# Connector-side-2.net
KiCad netlist of a schematic drawn in Altium Designer
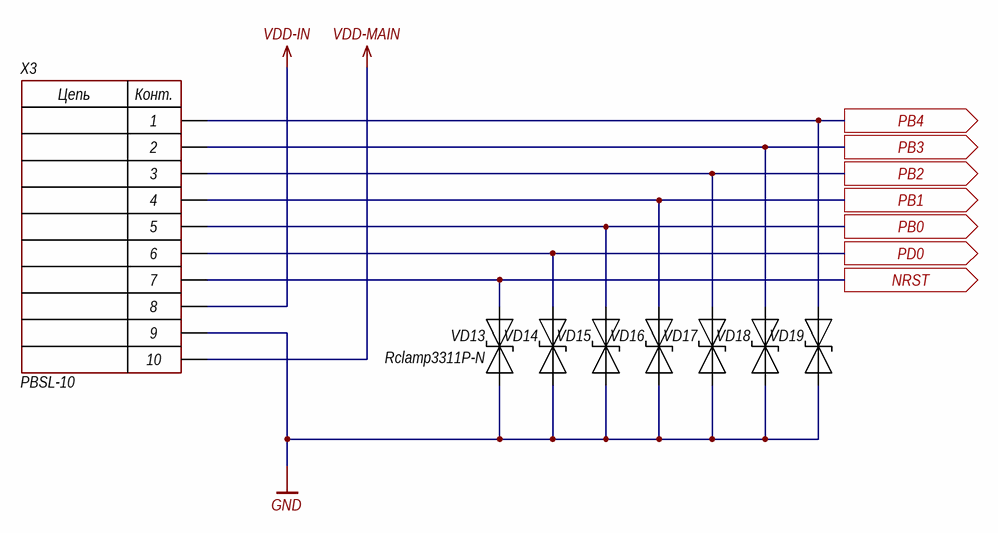
[diagram p0: Connector-side-2.SchDoc]

(export (version "E")
  (design (tool "Eeschema 10.0.6"))
  (components
    (comp (ref "VD13")
      (value "Rclamp3311P-N")
      (footprint "DFN1006-2")
      (fields (field (name "MANUFACTURER") "BORN"))
      (libsource (lib "Diods") (part "TVS-diod"))
    )
    (comp (ref "VD14")
      (value "Rclamp3311P-N")
      (footprint "DFN1006-2")
      (fields (field (name "MANUFACTURER") "BORN"))
      (libsource (lib "Diods") (part "TVS-diod"))
    )
    (comp (ref "VD15")
      (value "Rclamp3311P-N")
      (footprint "DFN1006-2")
      (fields (field (name "MANUFACTURER") "BORN"))
      (libsource (lib "Diods") (part "TVS-diod"))
    )
    (comp (ref "VD16")
      (value "Rclamp3311P-N")
      (footprint "DFN1006-2")
      (fields (field (name "MANUFACTURER") "BORN"))
      (libsource (lib "Diods") (part "TVS-diod"))
    )
    (comp (ref "VD17")
      (value "Rclamp3311P-N")
      (footprint "DFN1006-2")
      (fields (field (name "MANUFACTURER") "BORN"))
      (libsource (lib "Diods") (part "TVS-diod"))
    )
    (comp (ref "VD18")
      (value "Rclamp3311P-N")
      (footprint "DFN1006-2")
      (fields (field (name "MANUFACTURER") "BORN"))
      (libsource (lib "Diods") (part "TVS-diod"))
    )
    (comp (ref "VD19")
      (value "Rclamp3311P-N")
      (footprint "DFN1006-2")
      (fields (field (name "MANUFACTURER") "BORN"))
      (libsource (lib "Diods") (part "TVS-diod"))
    )
    (comp (ref "X3")
      (value "PBSL-10")
      (footprint "CON: PBSL-10")
      (libsource (lib "Connectors") (part "10-Connector"))
    )
  )
  (nets
    (net (code "1") (name "/NRST") (class "Default")
      (node (ref "VD13") (pin "2") (pinfunction "C_2") (pintype "passive"))
      (node (ref "X3") (pin "7") (pinfunction "7_7") (pintype "passive"))
    )
    (net (code "2") (name "/PB0") (class "Default")
      (node (ref "VD15") (pin "2") (pinfunction "C_2") (pintype "passive"))
      (node (ref "X3") (pin "5") (pinfunction "5_5") (pintype "passive"))
    )
    (net (code "3") (name "/PB1") (class "Default")
      (node (ref "VD16") (pin "2") (pinfunction "C_2") (pintype "passive"))
      (node (ref "X3") (pin "4") (pinfunction "4_4") (pintype "passive"))
    )
    (net (code "4") (name "/PB2") (class "Default")
      (node (ref "VD17") (pin "2") (pinfunction "C_2") (pintype "passive"))
      (node (ref "X3") (pin "3") (pinfunction "3_3") (pintype "passive"))
    )
    (net (code "5") (name "/PB3") (class "Default")
      (node (ref "VD18") (pin "2") (pinfunction "C_2") (pintype "passive"))
      (node (ref "X3") (pin "2") (pinfunction "2_2") (pintype "passive"))
    )
    (net (code "6") (name "/PB4") (class "Default")
      (node (ref "VD19") (pin "2") (pinfunction "C_2") (pintype "passive"))
      (node (ref "X3") (pin "1") (pinfunction "1_1") (pintype "passive"))
    )
    (net (code "7") (name "/PD0") (class "Default")
      (node (ref "VD14") (pin "2") (pinfunction "C_2") (pintype "passive"))
      (node (ref "X3") (pin "6") (pinfunction "6_6") (pintype "passive"))
    )
    (net (code "8") (name "GND") (class "Default")
      (node (ref "VD13") (pin "1") (pinfunction "A_1") (pintype "passive"))
      (node (ref "VD14") (pin "1") (pinfunction "A_1") (pintype "passive"))
      (node (ref "VD15") (pin "1") (pinfunction "A_1") (pintype "passive"))
      (node (ref "VD16") (pin "1") (pinfunction "A_1") (pintype "passive"))
      (node (ref "VD17") (pin "1") (pinfunction "A_1") (pintype "passive"))
      (node (ref "VD18") (pin "1") (pinfunction "A_1") (pintype "passive"))
      (node (ref "VD19") (pin "1") (pinfunction "A_1") (pintype "passive"))
      (node (ref "X3") (pin "9") (pinfunction "9_9") (pintype "passive"))
    )
    (net (code "9") (name "VDD-IN") (class "Default")
      (node (ref "X3") (pin "8") (pinfunction "8_8") (pintype "passive"))
    )
    (net (code "10") (name "VDD-MAIN") (class "Default")
      (node (ref "X3") (pin "10") (pinfunction "10_10") (pintype "passive"))
    )
  )
)
